# SoC_224-229_ADC_DAC.net
KiCad netlist of a schematic drawn in Altium Designer
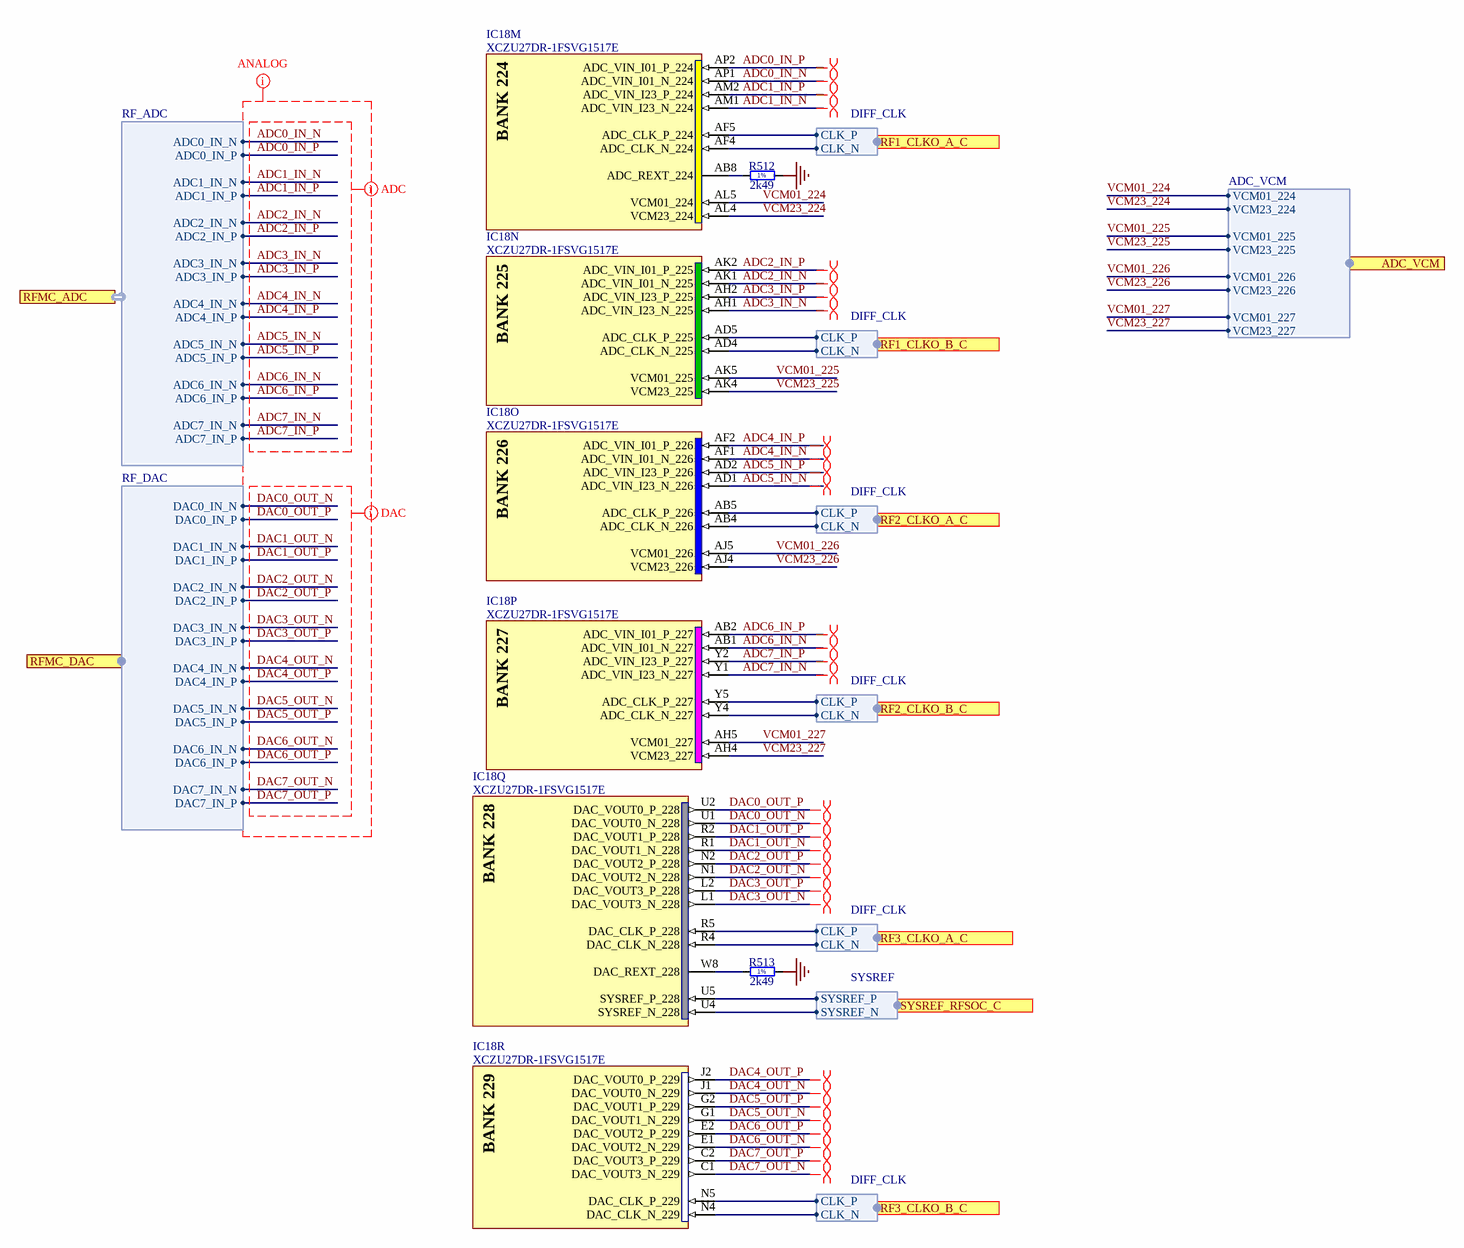
[diagram p0: SoC_224-229_ADC_DAC.SchDoc]

(export (version "E")
  (design (tool "Eeschema 10.0.6"))
  (components
    (comp (ref "IC18")
      (value "XCZU27DR-1FSVG1517E")
      (footprint "XILINX_FSVG1517 (XCZU27DR)")
      (fields (field (name "MANUFACTURER") "XILINX") (field (name "AUTHOR") "CERN DEM MR"))
      (libsource (lib "ICs And Semiconductors") (part "XCZU27DR-1FSVG1517E"))
    )
    (comp (ref "R512")
      (value "2k49")
      (footprint "RESC1608X55N")
      (description "Resistor - 1%")
      (fields
        (field (name "PART NUMBER") "R0603_2K49_1%_0.063W_50PPM")
        (field (name "POWER") "0.1W")
        (field (name "AUTHOR") "CERN DEM JLC")
      )
      (libsource (lib "Resistors") (part "Resistor - 1%"))
    )
    (comp (ref "R513")
      (value "2k49")
      (footprint "RESC1608X55N")
      (description "Resistor - 1%")
      (fields
        (field (name "PART NUMBER") "R0603_2K49_1%_0.063W_50PPM")
        (field (name "POWER") "0.1W")
        (field (name "AUTHOR") "CERN DEM JLC")
      )
      (libsource (lib "Resistors") (part "Resistor - 1%"))
    )
  )
  (nets
    (net (code "6") (name "/ADC0_IN_N") (class "Default")
      (node (ref "IC18") (pin "AP1") (pinfunction "ADC_VIN_I01_N_224_AP1") (pintype "input"))
    )
    (net (code "7") (name "/ADC0_IN_P") (class "Default")
      (node (ref "IC18") (pin "AP2") (pinfunction "ADC_VIN_I01_P_224_AP2") (pintype "input"))
    )
    (net (code "8") (name "/ADC1_IN_N") (class "Default")
      (node (ref "IC18") (pin "AM1") (pinfunction "ADC_VIN_I23_N_224_AM1") (pintype "input"))
    )
    (net (code "9") (name "/ADC1_IN_P") (class "Default")
      (node (ref "IC18") (pin "AM2") (pinfunction "ADC_VIN_I23_P_224_AM2") (pintype "input"))
    )
    (net (code "10") (name "/ADC2_IN_N") (class "Default")
      (node (ref "IC18") (pin "AK1") (pinfunction "ADC_VIN_I01_N_225_AK1") (pintype "input"))
    )
    (net (code "11") (name "/ADC2_IN_P") (class "Default")
      (node (ref "IC18") (pin "AK2") (pinfunction "ADC_VIN_I01_P_225_AK2") (pintype "input"))
    )
    (net (code "12") (name "/ADC3_IN_N") (class "Default")
      (node (ref "IC18") (pin "AH1") (pinfunction "ADC_VIN_I23_N_225_AH1") (pintype "input"))
    )
    (net (code "13") (name "/ADC3_IN_P") (class "Default")
      (node (ref "IC18") (pin "AH2") (pinfunction "ADC_VIN_I23_P_225_AH2") (pintype "input"))
    )
    (net (code "14") (name "/ADC4_IN_N") (class "Default")
      (node (ref "IC18") (pin "AF1") (pinfunction "ADC_VIN_I01_N_226_AF1") (pintype "input"))
    )
    (net (code "15") (name "/ADC4_IN_P") (class "Default")
      (node (ref "IC18") (pin "AF2") (pinfunction "ADC_VIN_I01_P_226_AF2") (pintype "input"))
    )
    (net (code "16") (name "/ADC5_IN_N") (class "Default")
      (node (ref "IC18") (pin "AD1") (pinfunction "ADC_VIN_I23_N_226_AD1") (pintype "input"))
    )
    (net (code "17") (name "/ADC5_IN_P") (class "Default")
      (node (ref "IC18") (pin "AD2") (pinfunction "ADC_VIN_I23_P_226_AD2") (pintype "input"))
    )
    (net (code "18") (name "/ADC6_IN_N") (class "Default")
      (node (ref "IC18") (pin "AB1") (pinfunction "ADC_VIN_I01_N_227_AB1") (pintype "input"))
    )
    (net (code "19") (name "/ADC6_IN_P") (class "Default")
      (node (ref "IC18") (pin "AB2") (pinfunction "ADC_VIN_I01_P_227_AB2") (pintype "input"))
    )
    (net (code "20") (name "/ADC7_IN_N") (class "Default")
      (node (ref "IC18") (pin "Y1") (pinfunction "ADC_VIN_I23_N_227_Y1") (pintype "input"))
    )
    (net (code "21") (name "/ADC7_IN_P") (class "Default")
      (node (ref "IC18") (pin "Y2") (pinfunction "ADC_VIN_I23_P_227_Y2") (pintype "input"))
    )
    (net (code "22") (name "/DAC0_OUT_N") (class "Default")
      (node (ref "IC18") (pin "U1") (pinfunction "DAC_VOUT0_N_228_U1") (pintype "output"))
    )
    (net (code "23") (name "/DAC0_OUT_P") (class "Default")
      (node (ref "IC18") (pin "U2") (pinfunction "DAC_VOUT0_P_228_U2") (pintype "output"))
    )
    (net (code "24") (name "/DAC1_OUT_N") (class "Default")
      (node (ref "IC18") (pin "R1") (pinfunction "DAC_VOUT1_N_228_R1") (pintype "output"))
    )
    (net (code "25") (name "/DAC1_OUT_P") (class "Default")
      (node (ref "IC18") (pin "R2") (pinfunction "DAC_VOUT1_P_228_R2") (pintype "output"))
    )
    (net (code "26") (name "/DAC2_OUT_N") (class "Default")
      (node (ref "IC18") (pin "N1") (pinfunction "DAC_VOUT2_N_228_N1") (pintype "output"))
    )
    (net (code "27") (name "/DAC2_OUT_P") (class "Default")
      (node (ref "IC18") (pin "N2") (pinfunction "DAC_VOUT2_P_228_N2") (pintype "output"))
    )
    (net (code "28") (name "/DAC3_OUT_N") (class "Default")
      (node (ref "IC18") (pin "L1") (pinfunction "DAC_VOUT3_N_228_L1") (pintype "output"))
    )
    (net (code "29") (name "/DAC3_OUT_P") (class "Default")
      (node (ref "IC18") (pin "L2") (pinfunction "DAC_VOUT3_P_228_L2") (pintype "output"))
    )
    (net (code "30") (name "/DAC4_OUT_N") (class "Default")
      (node (ref "IC18") (pin "J1") (pinfunction "DAC_VOUT0_N_229_J1") (pintype "output"))
    )
    (net (code "31") (name "/DAC4_OUT_P") (class "Default")
      (node (ref "IC18") (pin "J2") (pinfunction "DAC_VOUT0_P_229_J2") (pintype "output"))
    )
    (net (code "32") (name "/DAC5_OUT_N") (class "Default")
      (node (ref "IC18") (pin "G1") (pinfunction "DAC_VOUT1_N_229_G1") (pintype "output"))
    )
    (net (code "33") (name "/DAC5_OUT_P") (class "Default")
      (node (ref "IC18") (pin "G2") (pinfunction "DAC_VOUT1_P_229_G2") (pintype "output"))
    )
    (net (code "34") (name "/DAC6_OUT_N") (class "Default")
      (node (ref "IC18") (pin "E1") (pinfunction "DAC_VOUT2_N_229_E1") (pintype "output"))
    )
    (net (code "35") (name "/DAC6_OUT_P") (class "Default")
      (node (ref "IC18") (pin "E2") (pinfunction "DAC_VOUT2_P_229_E2") (pintype "output"))
    )
    (net (code "36") (name "/DAC7_OUT_N") (class "Default")
      (node (ref "IC18") (pin "C1") (pinfunction "DAC_VOUT3_N_229_C1") (pintype "output"))
    )
    (net (code "37") (name "/DAC7_OUT_P") (class "Default")
      (node (ref "IC18") (pin "C2") (pinfunction "DAC_VOUT3_P_229_C2") (pintype "output"))
    )
    (net (code "38") (name "/SYSREF_N") (class "Default")
      (node (ref "IC18") (pin "U4") (pinfunction "SYSREF_N_228_U4") (pintype "input"))
    )
    (net (code "39") (name "/SYSREF_P") (class "Default")
      (node (ref "IC18") (pin "U5") (pinfunction "SYSREF_P_228_U5") (pintype "input"))
    )
    (net (code "40") (name "/VCM01_224") (class "Default")
      (node (ref "IC18") (pin "AL5") (pinfunction "VCM01_224_AL5") (pintype "input"))
    )
    (net (code "41") (name "/VCM01_225") (class "Default")
      (node (ref "IC18") (pin "AK5") (pinfunction "VCM01_225_AK5") (pintype "input"))
    )
    (net (code "42") (name "/VCM01_226") (class "Default")
      (node (ref "IC18") (pin "AJ5") (pinfunction "VCM01_226_AJ5") (pintype "input"))
    )
    (net (code "43") (name "/VCM01_227") (class "Default")
      (node (ref "IC18") (pin "AH5") (pinfunction "VCM01_227_AH5") (pintype "input"))
    )
    (net (code "44") (name "/VCM23_224") (class "Default")
      (node (ref "IC18") (pin "AL4") (pinfunction "VCM23_224_AL4") (pintype "input"))
    )
    (net (code "45") (name "/VCM23_225") (class "Default")
      (node (ref "IC18") (pin "AK4") (pinfunction "VCM23_225_AK4") (pintype "input"))
    )
    (net (code "46") (name "/VCM23_226") (class "Default")
      (node (ref "IC18") (pin "AJ4") (pinfunction "VCM23_226_AJ4") (pintype "input"))
    )
    (net (code "47") (name "/VCM23_227") (class "Default")
      (node (ref "IC18") (pin "AH4") (pinfunction "VCM23_227_AH4") (pintype "input"))
    )
    (net (code "53") (name "GND") (class "Default")
      (node (ref "R512") (pin "2") (pinfunction "2_2") (pintype "passive"))
      (node (ref "R513") (pin "2") (pinfunction "2_2") (pintype "passive"))
    )
    (net (code "54") (name "Net-(IC18M-ADC_REXT_224)") (class "Default")
      (node (ref "IC18") (pin "AB8") (pinfunction "ADC_REXT_224_AB8") (pintype "passive"))
      (node (ref "R512") (pin "1") (pinfunction "1_1") (pintype "passive"))
    )
    (net (code "55") (name "Net-(IC18Q-DAC_REXT_228)") (class "Default")
      (node (ref "IC18") (pin "W8") (pinfunction "DAC_REXT_228_W8") (pintype "passive"))
      (node (ref "R513") (pin "1") (pinfunction "1_1") (pintype "passive"))
    )
    (net (code "56") (name "unconnected-(IC18M-ADC_CLK_N_224-PadAF4)") (class "Default")
      (node (ref "IC18") (pin "AF4") (pinfunction "ADC_CLK_N_224_AF4") (pintype "input"))
    )
    (net (code "57") (name "unconnected-(IC18M-ADC_CLK_P_224-PadAF5)") (class "Default")
      (node (ref "IC18") (pin "AF5") (pinfunction "ADC_CLK_P_224_AF5") (pintype "input"))
    )
    (net (code "58") (name "unconnected-(IC18N-ADC_CLK_N_225-PadAD4)") (class "Default")
      (node (ref "IC18") (pin "AD4") (pinfunction "ADC_CLK_N_225_AD4") (pintype "input"))
    )
    (net (code "59") (name "unconnected-(IC18N-ADC_CLK_P_225-PadAD5)") (class "Default")
      (node (ref "IC18") (pin "AD5") (pinfunction "ADC_CLK_P_225_AD5") (pintype "input"))
    )
    (net (code "60") (name "unconnected-(IC18O-ADC_CLK_N_226-PadAB4)") (class "Default")
      (node (ref "IC18") (pin "AB4") (pinfunction "ADC_CLK_N_226_AB4") (pintype "input"))
    )
    (net (code "61") (name "unconnected-(IC18O-ADC_CLK_P_226-PadAB5)") (class "Default")
      (node (ref "IC18") (pin "AB5") (pinfunction "ADC_CLK_P_226_AB5") (pintype "input"))
    )
    (net (code "62") (name "unconnected-(IC18P-ADC_CLK_N_227-PadY4)") (class "Default")
      (node (ref "IC18") (pin "Y4") (pinfunction "ADC_CLK_N_227_Y4") (pintype "input"))
    )
    (net (code "63") (name "unconnected-(IC18P-ADC_CLK_P_227-PadY5)") (class "Default")
      (node (ref "IC18") (pin "Y5") (pinfunction "ADC_CLK_P_227_Y5") (pintype "input"))
    )
    (net (code "64") (name "unconnected-(IC18Q-DAC_CLK_N_228-PadR4)") (class "Default")
      (node (ref "IC18") (pin "R4") (pinfunction "DAC_CLK_N_228_R4") (pintype "input"))
    )
    (net (code "65") (name "unconnected-(IC18Q-DAC_CLK_P_228-PadR5)") (class "Default")
      (node (ref "IC18") (pin "R5") (pinfunction "DAC_CLK_P_228_R5") (pintype "input"))
    )
    (net (code "66") (name "unconnected-(IC18R-DAC_CLK_N_229-PadN4)") (class "Default")
      (node (ref "IC18") (pin "N4") (pinfunction "DAC_CLK_N_229_N4") (pintype "input"))
    )
    (net (code "67") (name "unconnected-(IC18R-DAC_CLK_P_229-PadN5)") (class "Default")
      (node (ref "IC18") (pin "N5") (pinfunction "DAC_CLK_P_229_N5") (pintype "input"))
    )
  )
)
